# LightControl5C.net
KiCad netlist of a schematic drawn in EAGLE
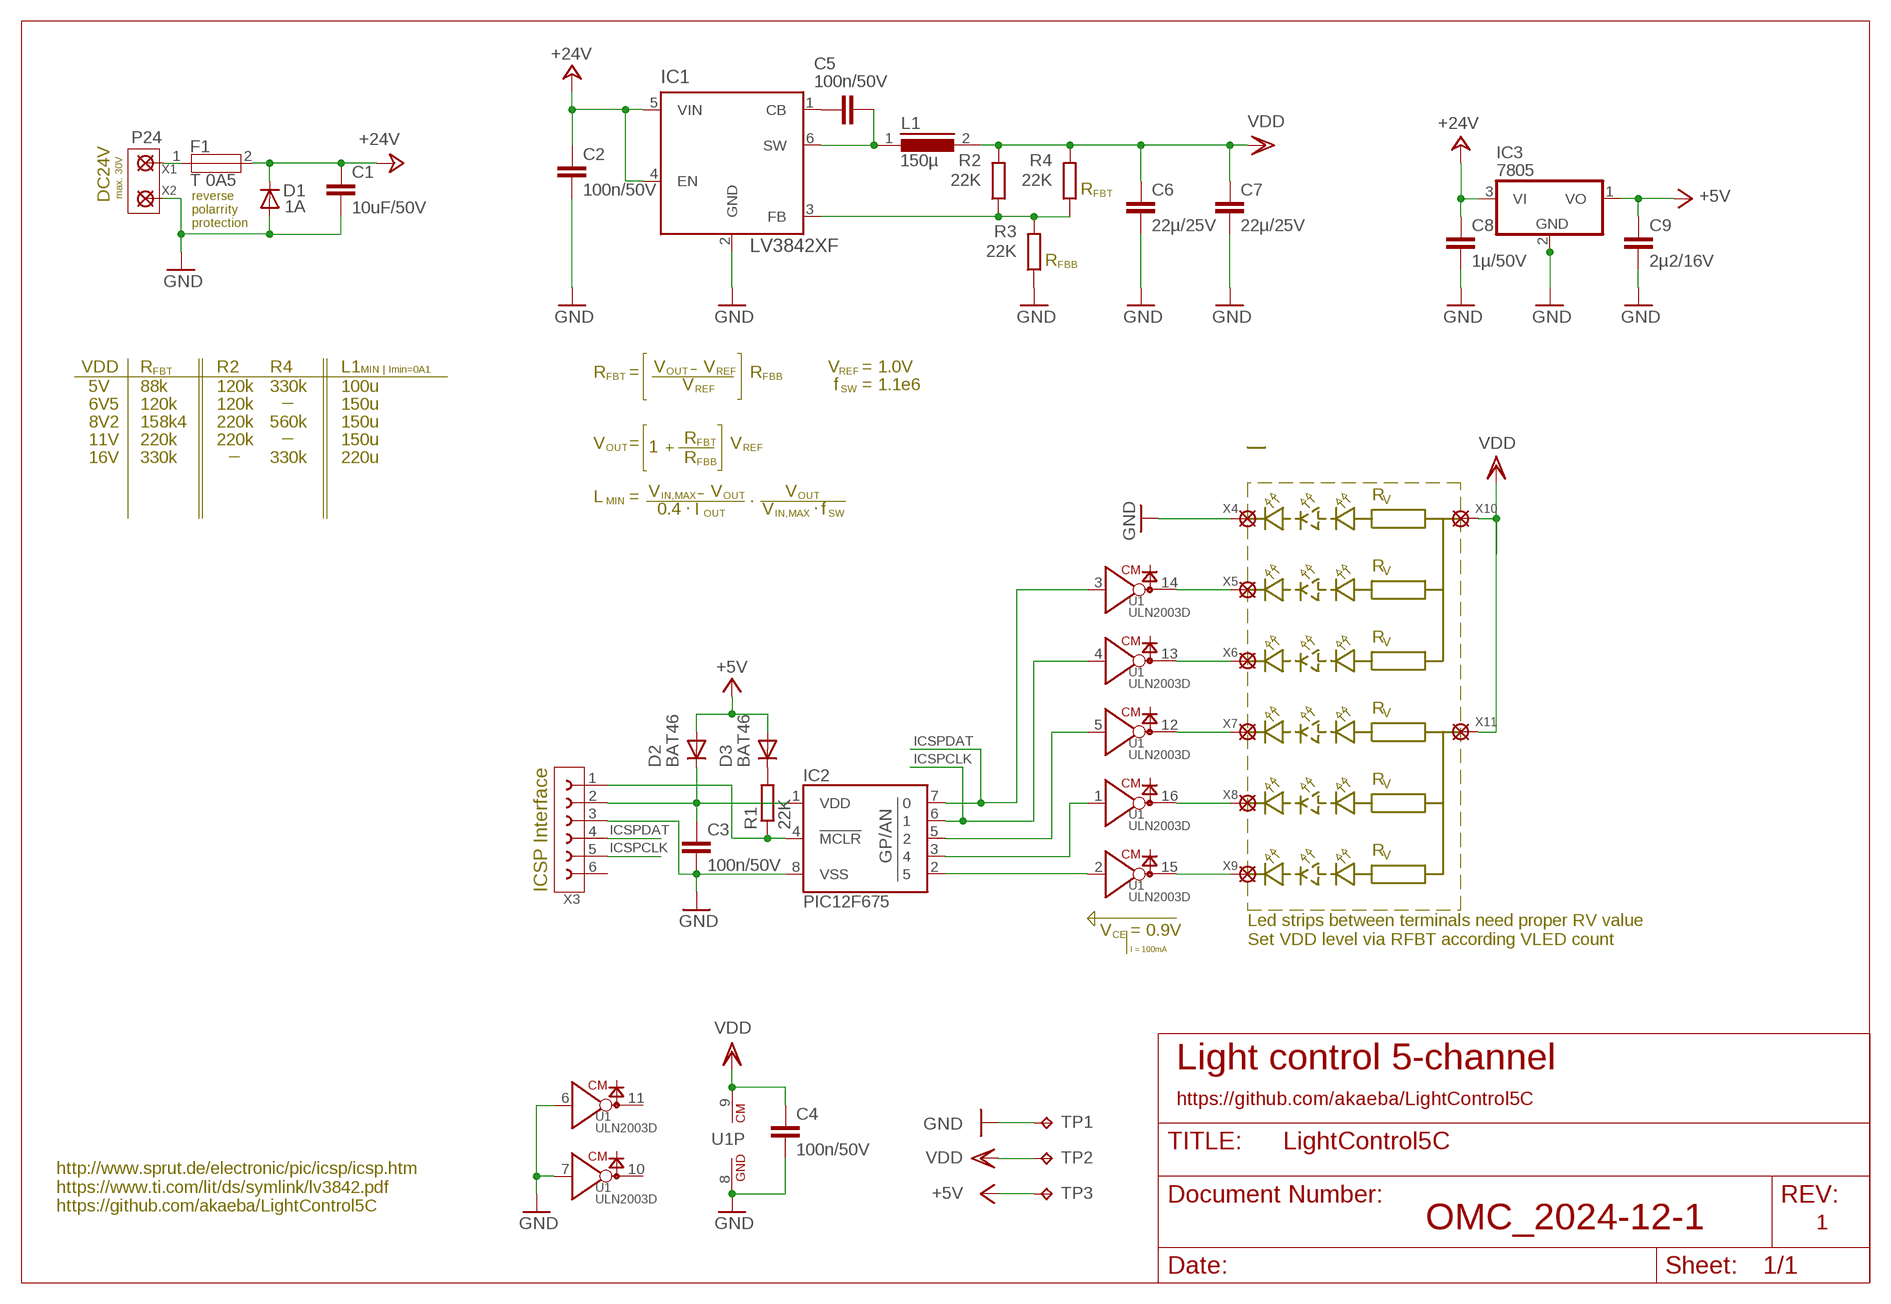
[diagram p0: schematic, sheet 1]

(export (version "E")
  (design (tool "Eeschema 10.0.6"))
  (components
    (comp (ref "C1")
      (value "10uF/50V")
      (footprint "eagle-import:C2220K")
      (libsource (lib "eagle-import") (part "C-EUC2220K"))
    )
    (comp (ref "C2")
      (value "100n/50V")
      (footprint "eagle-import:0805")
      (libsource (lib "eagle-import") (part "X7R-0805-100000P"))
    )
    (comp (ref "C3")
      (value "100n/50V")
      (footprint "eagle-import:0805")
      (libsource (lib "eagle-import") (part "X7R-0805-100000P"))
    )
    (comp (ref "C4")
      (value "100n/50V")
      (footprint "eagle-import:0805")
      (libsource (lib "eagle-import") (part "X7R-0805-100000P"))
    )
    (comp (ref "C5")
      (value "100n/50V")
      (footprint "eagle-import:0805")
      (libsource (lib "eagle-import") (part "X7R-0805-100000P"))
    )
    (comp (ref "C6")
      (value "22µ/25V")
      (footprint "eagle-import:1210")
      (libsource (lib "eagle-import") (part "X5R-1210-22000000P"))
    )
    (comp (ref "C7")
      (value "22µ/25V")
      (footprint "eagle-import:1210")
      (libsource (lib "eagle-import") (part "X5R-1210-22000000P"))
    )
    (comp (ref "C8")
      (value "1µ/50V")
      (footprint "eagle-import:0805")
      (libsource (lib "eagle-import") (part "X7R-0805-1000000P"))
    )
    (comp (ref "C9")
      (value "2µ2/16V")
      (footprint "eagle-import:0805")
      (libsource (lib "eagle-import") (part "X7R-0805-2200000P"))
    )
    (comp (ref "D1")
      (value "1A")
      (footprint "eagle-import:DO214AC")
      (libsource (lib "eagle-import") (part "RS1B"))
    )
    (comp (ref "D2")
      (value "BAT46")
      (footprint "eagle-import:SOD123")
      (libsource (lib "eagle-import") (part "BAT46W"))
    )
    (comp (ref "D3")
      (value "BAT46")
      (footprint "eagle-import:SOD123")
      (libsource (lib "eagle-import") (part "BAT46W"))
    )
    (comp (ref "F1")
      (value "T 0A5")
      (footprint "eagle-import:OMT125")
      (libsource (lib "eagle-import") (part "OMT-125V-T0A75"))
    )
    (comp (ref "IC1")
      (value "LV3842XF")
      (footprint "eagle-import:SOT23-6")
      (libsource (lib "eagle-import") (part "LV3842"))
    )
    (comp (ref "IC2")
      (value "PIC12F675")
      (footprint "eagle-import:SOIC08")
      (libsource (lib "eagle-import") (part "PIC12F675SN"))
    )
    (comp (ref "IC3")
      (value "7805")
      (footprint "eagle-import:SOT89W")
      (libsource (lib "eagle-import") (part "78LACY05"))
    )
    (comp (ref "L1")
      (value "150µ")
      (footprint "eagle-import:PISM")
      (libsource (lib "eagle-import") (part "PISM-150U"))
    )
    (comp (ref "R1")
      (value "22K")
      (footprint "eagle-import:0805")
      (libsource (lib "eagle-import") (part "RC0805-22000"))
    )
    (comp (ref "R2")
      (value "22K")
      (footprint "eagle-import:0805")
      (libsource (lib "eagle-import") (part "RC0805-22000"))
    )
    (comp (ref "R3")
      (value "22K")
      (footprint "eagle-import:0805")
      (libsource (lib "eagle-import") (part "RC0805-22000"))
    )
    (comp (ref "R4")
      (value "22K")
      (footprint "eagle-import:0805")
      (libsource (lib "eagle-import") (part "RC0805-22000"))
    )
    (comp (ref "TP1")
      (value "TPB1,27")
      (footprint "eagle-import:B1,27")
      (fields (field (name "TP_SIGNAL_NAME") "GND"))
      (libsource (lib "eagle-import") (part "TPB1,27"))
    )
    (comp (ref "TP2")
      (value "TPB1,27")
      (footprint "eagle-import:B1,27")
      (fields (field (name "TP_SIGNAL_NAME") "GND"))
      (libsource (lib "eagle-import") (part "TPB1,27"))
    )
    (comp (ref "TP3")
      (value "TPB1,27")
      (footprint "eagle-import:B1,27")
      (fields (field (name "TP_SIGNAL_NAME") "GND"))
      (libsource (lib "eagle-import") (part "TPB1,27"))
    )
    (comp (ref "U1")
      (value "ULN2003D")
      (footprint "eagle-import:SOIC16")
      (libsource (lib "eagle-import") (part "ULN200D3"))
    )
    (comp (ref "X1")
      (value "Footprint")
      (footprint "eagle-import:L38W19X1")
      (libsource (lib "eagle-import") (part "1X1S-L38W19"))
    )
    (comp (ref "X2")
      (value "Footprint")
      (footprint "eagle-import:L38W19X1")
      (libsource (lib "eagle-import") (part "1X1S-L38W19"))
    )
    (comp (ref "X3")
      (value "FLE-103-01")
      (footprint "eagle-import:FLE-103")
      (libsource (lib "eagle-import") (part "BOXHD-06-SMT-1.27"))
    )
    (comp (ref "X4")
      (value "Footprint")
      (footprint "eagle-import:L38W19X1")
      (libsource (lib "eagle-import") (part "1X1S-L38W19"))
    )
    (comp (ref "X5")
      (value "Footprint")
      (footprint "eagle-import:L38W19X1")
      (libsource (lib "eagle-import") (part "1X1S-L38W19"))
    )
    (comp (ref "X6")
      (value "Footprint")
      (footprint "eagle-import:L38W19X1")
      (libsource (lib "eagle-import") (part "1X1S-L38W19"))
    )
    (comp (ref "X7")
      (value "Footprint")
      (footprint "eagle-import:L38W19X1")
      (libsource (lib "eagle-import") (part "1X1S-L38W19"))
    )
    (comp (ref "X8")
      (value "Footprint")
      (footprint "eagle-import:L38W19X1")
      (libsource (lib "eagle-import") (part "1X1S-L38W19"))
    )
    (comp (ref "X9")
      (value "Footprint")
      (footprint "eagle-import:L38W19X1")
      (libsource (lib "eagle-import") (part "1X1S-L38W19"))
    )
    (comp (ref "X10")
      (value "Footprint")
      (footprint "eagle-import:L38W19X1")
      (libsource (lib "eagle-import") (part "1X1S-L38W19"))
    )
    (comp (ref "X11")
      (value "Footprint")
      (footprint "eagle-import:L38W19X1")
      (libsource (lib "eagle-import") (part "1X1S-L38W19"))
    )
  )
  (nets
    (net (code "1") (name "+5V") (class "Default")
      (node (ref "C9") (pin "1") (pinfunction "1_1") (pintype "passive"))
      (node (ref "D2") (pin "A") (pinfunction "A_A") (pintype "passive"))
      (node (ref "D3") (pin "A") (pinfunction "A_A") (pintype "passive"))
      (node (ref "IC3") (pin "1") (pinfunction "VO_1") (pintype "power_in"))
      (node (ref "TP3") (pin "TP") (pinfunction "TP_TP") (pintype "input"))
    )
    (net (code "2") (name "+24V") (class "Default")
      (node (ref "C1") (pin "1") (pinfunction "1_1") (pintype "passive"))
      (node (ref "C2") (pin "1") (pinfunction "1_1") (pintype "passive"))
      (node (ref "C8") (pin "1") (pinfunction "1_1") (pintype "passive"))
      (node (ref "D1") (pin "C") (pinfunction "C_C") (pintype "passive"))
      (node (ref "F1") (pin "2") (pinfunction "P$2_2") (pintype "passive"))
      (node (ref "IC1") (pin "4") (pinfunction "EN_4") (pintype "passive"))
      (node (ref "IC1") (pin "5") (pinfunction "VIN_5") (pintype "power_in"))
      (node (ref "IC3") (pin "3") (pinfunction "VI_3") (pintype "input"))
    )
    (net (code "3") (name "/ICSPCLK") (class "Default")
      (node (ref "IC2") (pin "6") (pinfunction "1_6") (pintype "bidirectional"))
      (node (ref "U1") (pin "4") (pinfunction "IN_4") (pintype "input"))
      (node (ref "X3") (pin "5") (pinfunction "P$1_5") (pintype "bidirectional"))
    )
    (net (code "4") (name "/ICSPDAT") (class "Default")
      (node (ref "IC2") (pin "7") (pinfunction "0_7") (pintype "bidirectional"))
      (node (ref "U1") (pin "3") (pinfunction "IN_3") (pintype "input"))
      (node (ref "X3") (pin "4") (pinfunction "P$1_4") (pintype "bidirectional"))
    )
    (net (code "5") (name "/P24") (class "Default")
      (node (ref "F1") (pin "1") (pinfunction "P$1_1") (pintype "passive"))
      (node (ref "X1") (pin "1") (pinfunction "P$1_1") (pintype "bidirectional"))
    )
    (net (code "6") (name "GND") (class "Default")
      (node (ref "C1") (pin "2") (pinfunction "2_2") (pintype "passive"))
      (node (ref "C2") (pin "2") (pinfunction "2_2") (pintype "passive"))
      (node (ref "C3") (pin "2") (pinfunction "2_2") (pintype "passive"))
      (node (ref "C4") (pin "2") (pinfunction "2_2") (pintype "passive"))
      (node (ref "C6") (pin "2") (pinfunction "2_2") (pintype "passive"))
      (node (ref "C7") (pin "2") (pinfunction "2_2") (pintype "passive"))
      (node (ref "C8") (pin "2") (pinfunction "2_2") (pintype "passive"))
      (node (ref "C9") (pin "2") (pinfunction "2_2") (pintype "passive"))
      (node (ref "D1") (pin "A") (pinfunction "A_A") (pintype "passive"))
      (node (ref "IC1") (pin "2") (pinfunction "GND_2") (pintype "power_in"))
      (node (ref "IC2") (pin "8") (pinfunction "VSS_8") (pintype "power_in"))
      (node (ref "IC3") (pin "2") (pinfunction "GND_2") (pintype "power_in"))
      (node (ref "IC3") (pin "4") (pinfunction "GND_4") (pintype "power_in"))
      (node (ref "R3") (pin "1") (pinfunction "1_1") (pintype "passive"))
      (node (ref "TP1") (pin "TP") (pinfunction "TP_TP") (pintype "input"))
      (node (ref "U1") (pin "6") (pinfunction "IN_6") (pintype "input"))
      (node (ref "U1") (pin "7") (pinfunction "IN_7") (pintype "input"))
      (node (ref "U1") (pin "8") (pinfunction "GND_8") (pintype "power_in"))
      (node (ref "X2") (pin "1") (pinfunction "P$1_1") (pintype "bidirectional"))
      (node (ref "X3") (pin "3") (pinfunction "P$1_3") (pintype "bidirectional"))
      (node (ref "X4") (pin "1") (pinfunction "P$1_1") (pintype "bidirectional"))
    )
    (net (code "7") (name "Net-(D3-PadC)") (class "Default")
      (node (ref "D3") (pin "C") (pinfunction "C_C") (pintype "passive"))
      (node (ref "R1") (pin "2") (pinfunction "2_2") (pintype "passive"))
    )
    (net (code "8") (name "Net-(IC1-CB)") (class "Default")
      (node (ref "C5") (pin "1") (pinfunction "1_1") (pintype "passive"))
      (node (ref "IC1") (pin "1") (pinfunction "CB_1") (pintype "passive"))
    )
    (net (code "9") (name "Net-(IC1-FB)") (class "Default")
      (node (ref "IC1") (pin "3") (pinfunction "FB_3") (pintype "passive"))
      (node (ref "R2") (pin "1") (pinfunction "1_1") (pintype "passive"))
      (node (ref "R3") (pin "2") (pinfunction "2_2") (pintype "passive"))
      (node (ref "R4") (pin "1") (pinfunction "1_1") (pintype "passive"))
    )
    (net (code "10") (name "Net-(IC1-SW)") (class "Default")
      (node (ref "C5") (pin "2") (pinfunction "2_2") (pintype "passive"))
      (node (ref "IC1") (pin "6") (pinfunction "SW_6") (pintype "output"))
      (node (ref "L1") (pin "1") (pinfunction "1_1") (pintype "passive"))
    )
    (net (code "11") (name "Net-(IC2-2)") (class "Default")
      (node (ref "IC2") (pin "5") (pinfunction "2_5") (pintype "bidirectional"))
      (node (ref "U1") (pin "5") (pinfunction "IN_5") (pintype "input"))
    )
    (net (code "12") (name "Net-(IC2-4)") (class "Default")
      (node (ref "IC2") (pin "3") (pinfunction "4_3") (pintype "bidirectional"))
      (node (ref "U1") (pin "1") (pinfunction "IN_1") (pintype "input"))
    )
    (net (code "13") (name "Net-(IC2-5)") (class "Default")
      (node (ref "IC2") (pin "2") (pinfunction "5_2") (pintype "bidirectional"))
      (node (ref "U1") (pin "2") (pinfunction "IN_2") (pintype "input"))
    )
    (net (code "14") (name "Net-(IC2-VDD)") (class "Default")
      (node (ref "C3") (pin "1") (pinfunction "1_1") (pintype "passive"))
      (node (ref "D2") (pin "C") (pinfunction "C_C") (pintype "passive"))
      (node (ref "IC2") (pin "1") (pinfunction "VDD_1") (pintype "power_in"))
      (node (ref "X3") (pin "2") (pinfunction "P$1_2") (pintype "bidirectional"))
    )
    (net (code "15") (name "Net-(IC2-~{MCLR})") (class "Default")
      (node (ref "IC2") (pin "4") (pinfunction "~{MCLR}_4") (pintype "input"))
      (node (ref "R1") (pin "1") (pinfunction "1_1") (pintype "passive"))
      (node (ref "X3") (pin "1") (pinfunction "P$1_1") (pintype "bidirectional"))
    )
    (net (code "16") (name "Net-(U1A-OUT)") (class "Default")
      (node (ref "U1") (pin "16") (pinfunction "OUT_16") (pintype "open_collector"))
      (node (ref "X8") (pin "1") (pinfunction "P$1_1") (pintype "bidirectional"))
    )
    (net (code "17") (name "Net-(U1B-OUT)") (class "Default")
      (node (ref "U1") (pin "15") (pinfunction "OUT_15") (pintype "open_collector"))
      (node (ref "X9") (pin "1") (pinfunction "P$1_1") (pintype "bidirectional"))
    )
    (net (code "18") (name "Net-(U1C-OUT)") (class "Default")
      (node (ref "U1") (pin "13") (pinfunction "OUT_13") (pintype "open_collector"))
      (node (ref "X6") (pin "1") (pinfunction "P$1_1") (pintype "bidirectional"))
    )
    (net (code "19") (name "Net-(U1D-OUT)") (class "Default")
      (node (ref "U1") (pin "14") (pinfunction "OUT_14") (pintype "open_collector"))
      (node (ref "X5") (pin "1") (pinfunction "P$1_1") (pintype "bidirectional"))
    )
    (net (code "20") (name "Net-(U1E-OUT)") (class "Default")
      (node (ref "U1") (pin "12") (pinfunction "OUT_12") (pintype "open_collector"))
      (node (ref "X7") (pin "1") (pinfunction "P$1_1") (pintype "bidirectional"))
    )
    (net (code "21") (name "VDD") (class "Default")
      (node (ref "C4") (pin "1") (pinfunction "1_1") (pintype "passive"))
      (node (ref "C6") (pin "1") (pinfunction "1_1") (pintype "passive"))
      (node (ref "C7") (pin "1") (pinfunction "1_1") (pintype "passive"))
      (node (ref "L1") (pin "2") (pinfunction "2_2") (pintype "passive"))
      (node (ref "R2") (pin "2") (pinfunction "2_2") (pintype "passive"))
      (node (ref "R4") (pin "2") (pinfunction "2_2") (pintype "passive"))
      (node (ref "TP2") (pin "TP") (pinfunction "TP_TP") (pintype "input"))
      (node (ref "U1") (pin "9") (pinfunction "CM+_9") (pintype "power_in"))
      (node (ref "X10") (pin "1") (pinfunction "P$1_1") (pintype "bidirectional"))
      (node (ref "X11") (pin "1") (pinfunction "P$1_1") (pintype "bidirectional"))
    )
    (net (code "22") (name "unconnected-(U1F-OUT-Pad11)") (class "Default")
      (node (ref "U1") (pin "11") (pinfunction "OUT_11") (pintype "open_collector"))
    )
    (net (code "23") (name "unconnected-(U1G-OUT-Pad10)") (class "Default")
      (node (ref "U1") (pin "10") (pinfunction "OUT_10") (pintype "open_collector"))
    )
    (net (code "24") (name "unconnected-(X3F-P$1-Pad6)") (class "Default")
      (node (ref "X3") (pin "6") (pinfunction "P$1_6") (pintype "bidirectional"))
    )
  )
)
